# MCU_SUPPORT_CCU_HAS.net
KiCad netlist of a schematic drawn in Altium Designer
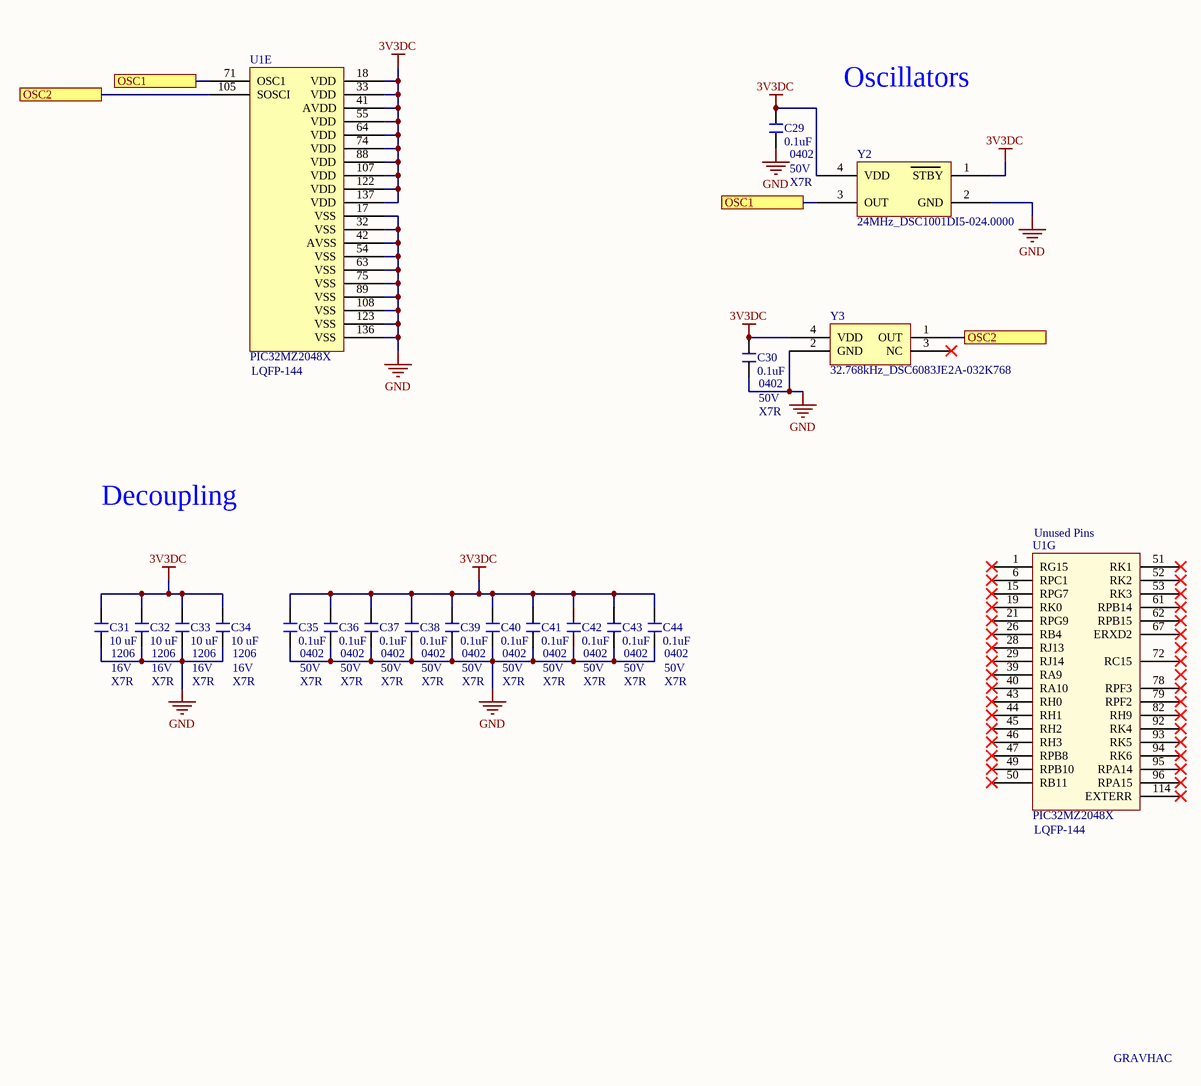
[diagram p0: MCU_SUPPORT_CCU_HAS.SchDoc]

(export (version "E")
  (design (tool "Eeschema 10.0.6"))
  (components
    (comp (ref "C29")
      (value "0.1uF")
      (footprint "NonPolar-0402")
      (libsource (lib "GravLib") (part "Cap - 0402"))
    )
    (comp (ref "C30")
      (value "0.1uF")
      (footprint "NonPolar-0402")
      (libsource (lib "GravLib") (part "Cap - 0402"))
    )
    (comp (ref "C31")
      (value "10 uF")
      (footprint "NONPOLAR-1206")
      (description "CGA5L1X7R1E106K160AE")
      (libsource (lib "GravLib") (part "Cap - 1206"))
    )
    (comp (ref "C32")
      (value "10 uF")
      (footprint "NONPOLAR-1206")
      (description "CGA5L1X7R1E106K160AE")
      (libsource (lib "GravLib") (part "Cap - 1206"))
    )
    (comp (ref "C33")
      (value "10 uF")
      (footprint "NONPOLAR-1206")
      (description "CGA5L1X7R1E106K160AE")
      (libsource (lib "GravLib") (part "Cap - 1206"))
    )
    (comp (ref "C34")
      (value "10 uF")
      (footprint "NONPOLAR-1206")
      (description "CGA5L1X7R1E106K160AE")
      (libsource (lib "GravLib") (part "Cap - 1206"))
    )
    (comp (ref "C35")
      (value "0.1uF")
      (footprint "NonPolar-0402")
      (libsource (lib "GravLib") (part "Cap - 0402"))
    )
    (comp (ref "C36")
      (value "0.1uF")
      (footprint "NonPolar-0402")
      (libsource (lib "GravLib") (part "Cap - 0402"))
    )
    (comp (ref "C37")
      (value "0.1uF")
      (footprint "NonPolar-0402")
      (libsource (lib "GravLib") (part "Cap - 0402"))
    )
    (comp (ref "C38")
      (value "0.1uF")
      (footprint "NonPolar-0402")
      (libsource (lib "GravLib") (part "Cap - 0402"))
    )
    (comp (ref "C39")
      (value "0.1uF")
      (footprint "NonPolar-0402")
      (libsource (lib "GravLib") (part "Cap - 0402"))
    )
    (comp (ref "C40")
      (value "0.1uF")
      (footprint "NonPolar-0402")
      (libsource (lib "GravLib") (part "Cap - 0402"))
    )
    (comp (ref "C41")
      (value "0.1uF")
      (footprint "NonPolar-0402")
      (libsource (lib "GravLib") (part "Cap - 0402"))
    )
    (comp (ref "C42")
      (value "0.1uF")
      (footprint "NonPolar-0402")
      (libsource (lib "GravLib") (part "Cap - 0402"))
    )
    (comp (ref "C43")
      (value "0.1uF")
      (footprint "NonPolar-0402")
      (libsource (lib "GravLib") (part "Cap - 0402"))
    )
    (comp (ref "C44")
      (value "0.1uF")
      (footprint "NonPolar-0402")
      (libsource (lib "GravLib") (part "Cap - 0402"))
    )
    (comp (ref "U1")
      (value "PIC32MZ2048X")
      (footprint "BIG_PIC32MZ")
      (libsource (lib "GravLib") (part "PIC32MZ2048X"))
    )
    (comp (ref "Y2")
      (value "24MHz_DSC1001DI5-024.0000")
      (footprint "12MHz_DSC1001DE2-012.0000")
      (libsource (lib "GravLib") (part "24MHz_DSC1001DI5-024.0000"))
    )
    (comp (ref "Y3")
      (value "32.768kHz_DSC6083JE2A-032K768")
      (footprint "32.768kHz_DSC6083JE2A-032K768")
      (libsource (lib "GravLib") (part "32.768kHz_DSC6083JE2A-032K768"))
    )
  )
  (nets
    (net (code "1") (name "/OSC1") (class "Default")
      (node (ref "U1") (pin "71") (pinfunction "OSC1_71") (pintype "passive"))
      (node (ref "Y2") (pin "3") (pinfunction "OUT_3") (pintype "passive"))
    )
    (net (code "2") (name "/OSC2") (class "Default")
      (node (ref "U1") (pin "105") (pinfunction "SOSCI_105") (pintype "passive"))
      (node (ref "Y3") (pin "1") (pinfunction "OUT_1") (pintype "passive"))
    )
    (net (code "3") (name "3V3DC") (class "Default")
      (node (ref "C29") (pin "2") (pinfunction "2_2") (pintype "passive"))
      (node (ref "C30") (pin "2") (pinfunction "2_2") (pintype "passive"))
      (node (ref "C31") (pin "2") (pinfunction "2_2") (pintype "passive"))
      (node (ref "C32") (pin "2") (pinfunction "2_2") (pintype "passive"))
      (node (ref "C33") (pin "2") (pinfunction "2_2") (pintype "passive"))
      (node (ref "C34") (pin "2") (pinfunction "2_2") (pintype "passive"))
      (node (ref "C35") (pin "2") (pinfunction "2_2") (pintype "passive"))
      (node (ref "C36") (pin "2") (pinfunction "2_2") (pintype "passive"))
      (node (ref "C37") (pin "2") (pinfunction "2_2") (pintype "passive"))
      (node (ref "C38") (pin "2") (pinfunction "2_2") (pintype "passive"))
      (node (ref "C39") (pin "2") (pinfunction "2_2") (pintype "passive"))
      (node (ref "C40") (pin "2") (pinfunction "2_2") (pintype "passive"))
      (node (ref "C41") (pin "2") (pinfunction "2_2") (pintype "passive"))
      (node (ref "C42") (pin "2") (pinfunction "2_2") (pintype "passive"))
      (node (ref "C43") (pin "2") (pinfunction "2_2") (pintype "passive"))
      (node (ref "C44") (pin "2") (pinfunction "2_2") (pintype "passive"))
      (node (ref "U1") (pin "107") (pinfunction "VDD_107") (pintype "passive"))
      (node (ref "U1") (pin "122") (pinfunction "VDD_122") (pintype "passive"))
      (node (ref "U1") (pin "137") (pinfunction "VDD_137") (pintype "passive"))
      (node (ref "U1") (pin "18") (pinfunction "VDD_18") (pintype "passive"))
      (node (ref "U1") (pin "33") (pinfunction "VDD_33") (pintype "passive"))
      (node (ref "U1") (pin "41") (pinfunction "AVDD_41") (pintype "passive"))
      (node (ref "U1") (pin "55") (pinfunction "VDD_55") (pintype "passive"))
      (node (ref "U1") (pin "64") (pinfunction "VDD_64") (pintype "passive"))
      (node (ref "U1") (pin "74") (pinfunction "VDD_74") (pintype "passive"))
      (node (ref "U1") (pin "88") (pinfunction "VDD_88") (pintype "passive"))
      (node (ref "Y2") (pin "1") (pinfunction "STBY_1") (pintype "passive"))
      (node (ref "Y2") (pin "4") (pinfunction "VDD_4") (pintype "passive"))
      (node (ref "Y3") (pin "4") (pinfunction "VDD_4") (pintype "passive"))
    )
    (net (code "4") (name "GND") (class "Default")
      (node (ref "C29") (pin "1") (pinfunction "1_1") (pintype "passive"))
      (node (ref "C30") (pin "1") (pinfunction "1_1") (pintype "passive"))
      (node (ref "C31") (pin "1") (pinfunction "1_1") (pintype "passive"))
      (node (ref "C32") (pin "1") (pinfunction "1_1") (pintype "passive"))
      (node (ref "C33") (pin "1") (pinfunction "1_1") (pintype "passive"))
      (node (ref "C34") (pin "1") (pinfunction "1_1") (pintype "passive"))
      (node (ref "C35") (pin "1") (pinfunction "1_1") (pintype "passive"))
      (node (ref "C36") (pin "1") (pinfunction "1_1") (pintype "passive"))
      (node (ref "C37") (pin "1") (pinfunction "1_1") (pintype "passive"))
      (node (ref "C38") (pin "1") (pinfunction "1_1") (pintype "passive"))
      (node (ref "C39") (pin "1") (pinfunction "1_1") (pintype "passive"))
      (node (ref "C40") (pin "1") (pinfunction "1_1") (pintype "passive"))
      (node (ref "C41") (pin "1") (pinfunction "1_1") (pintype "passive"))
      (node (ref "C42") (pin "1") (pinfunction "1_1") (pintype "passive"))
      (node (ref "C43") (pin "1") (pinfunction "1_1") (pintype "passive"))
      (node (ref "C44") (pin "1") (pinfunction "1_1") (pintype "passive"))
      (node (ref "U1") (pin "108") (pinfunction "VSS_108") (pintype "passive"))
      (node (ref "U1") (pin "123") (pinfunction "VSS_123") (pintype "passive"))
      (node (ref "U1") (pin "136") (pinfunction "VSS_136") (pintype "passive"))
      (node (ref "U1") (pin "17") (pinfunction "VSS_17") (pintype "passive"))
      (node (ref "U1") (pin "32") (pinfunction "VSS_32") (pintype "passive"))
      (node (ref "U1") (pin "42") (pinfunction "AVSS_42") (pintype "passive"))
      (node (ref "U1") (pin "54") (pinfunction "VSS_54") (pintype "passive"))
      (node (ref "U1") (pin "63") (pinfunction "VSS_63") (pintype "passive"))
      (node (ref "U1") (pin "75") (pinfunction "VSS_75") (pintype "passive"))
      (node (ref "U1") (pin "89") (pinfunction "VSS_89") (pintype "passive"))
      (node (ref "Y2") (pin "2") (pinfunction "GND_2") (pintype "passive"))
      (node (ref "Y3") (pin "2") (pinfunction "GND_2") (pintype "passive"))
    )
    (net (code "5") (name "unconnected-(U1G-ERXD2-Pad67)") (class "Default")
      (node (ref "U1") (pin "67") (pinfunction "ERXD2_67") (pintype "passive+no_connect"))
    )
    (net (code "6") (name "unconnected-(U1G-EXTERR-Pad114)") (class "Default")
      (node (ref "U1") (pin "114") (pinfunction "EXTERR_114") (pintype "passive+no_connect"))
    )
    (net (code "7") (name "unconnected-(U1G-RA9-Pad39)") (class "Default")
      (node (ref "U1") (pin "39") (pinfunction "RA9_39") (pintype "passive+no_connect"))
    )
    (net (code "8") (name "unconnected-(U1G-RA10-Pad40)") (class "Default")
      (node (ref "U1") (pin "40") (pinfunction "RA10_40") (pintype "passive+no_connect"))
    )
    (net (code "9") (name "unconnected-(U1G-RB4-Pad26)") (class "Default")
      (node (ref "U1") (pin "26") (pinfunction "RB4_26") (pintype "passive+no_connect"))
    )
    (net (code "10") (name "unconnected-(U1G-RB11-Pad50)") (class "Default")
      (node (ref "U1") (pin "50") (pinfunction "RB11_50") (pintype "passive+no_connect"))
    )
    (net (code "11") (name "unconnected-(U1G-RC15-Pad72)") (class "Default")
      (node (ref "U1") (pin "72") (pinfunction "RC15_72") (pintype "passive+no_connect"))
    )
    (net (code "12") (name "unconnected-(U1G-RG15-Pad1)") (class "Default")
      (node (ref "U1") (pin "1") (pinfunction "RG15_1") (pintype "passive+no_connect"))
    )
    (net (code "13") (name "unconnected-(U1G-RH0-Pad43)") (class "Default")
      (node (ref "U1") (pin "43") (pinfunction "RH0_43") (pintype "passive+no_connect"))
    )
    (net (code "14") (name "unconnected-(U1G-RH1-Pad44)") (class "Default")
      (node (ref "U1") (pin "44") (pinfunction "RH1_44") (pintype "passive+no_connect"))
    )
    (net (code "15") (name "unconnected-(U1G-RH2-Pad45)") (class "Default")
      (node (ref "U1") (pin "45") (pinfunction "RH2_45") (pintype "passive+no_connect"))
    )
    (net (code "16") (name "unconnected-(U1G-RH3-Pad46)") (class "Default")
      (node (ref "U1") (pin "46") (pinfunction "RH3_46") (pintype "passive+no_connect"))
    )
    (net (code "17") (name "unconnected-(U1G-RH9-Pad82)") (class "Default")
      (node (ref "U1") (pin "82") (pinfunction "RH9_82") (pintype "passive+no_connect"))
    )
    (net (code "18") (name "unconnected-(U1G-RJ13-Pad28)") (class "Default")
      (node (ref "U1") (pin "28") (pinfunction "RJ13_28") (pintype "passive+no_connect"))
    )
    (net (code "19") (name "unconnected-(U1G-RJ14-Pad29)") (class "Default")
      (node (ref "U1") (pin "29") (pinfunction "RJ14_29") (pintype "passive+no_connect"))
    )
    (net (code "20") (name "unconnected-(U1G-RK0-Pad19)") (class "Default")
      (node (ref "U1") (pin "19") (pinfunction "RK0_19") (pintype "passive+no_connect"))
    )
    (net (code "21") (name "unconnected-(U1G-RK1-Pad51)") (class "Default")
      (node (ref "U1") (pin "51") (pinfunction "RK1_51") (pintype "passive+no_connect"))
    )
    (net (code "22") (name "unconnected-(U1G-RK2-Pad52)") (class "Default")
      (node (ref "U1") (pin "52") (pinfunction "RK2_52") (pintype "passive+no_connect"))
    )
    (net (code "23") (name "unconnected-(U1G-RK3-Pad53)") (class "Default")
      (node (ref "U1") (pin "53") (pinfunction "RK3_53") (pintype "passive+no_connect"))
    )
    (net (code "24") (name "unconnected-(U1G-RK4-Pad92)") (class "Default")
      (node (ref "U1") (pin "92") (pinfunction "RK4_92") (pintype "passive+no_connect"))
    )
    (net (code "25") (name "unconnected-(U1G-RK5-Pad93)") (class "Default")
      (node (ref "U1") (pin "93") (pinfunction "RK5_93") (pintype "passive+no_connect"))
    )
    (net (code "26") (name "unconnected-(U1G-RK6-Pad94)") (class "Default")
      (node (ref "U1") (pin "94") (pinfunction "RK6_94") (pintype "passive+no_connect"))
    )
    (net (code "27") (name "unconnected-(U1G-RPA14-Pad95)") (class "Default")
      (node (ref "U1") (pin "95") (pinfunction "RPA14_95") (pintype "passive+no_connect"))
    )
    (net (code "28") (name "unconnected-(U1G-RPA15-Pad96)") (class "Default")
      (node (ref "U1") (pin "96") (pinfunction "RPA15_96") (pintype "passive+no_connect"))
    )
    (net (code "29") (name "unconnected-(U1G-RPB8-Pad47)") (class "Default")
      (node (ref "U1") (pin "47") (pinfunction "RPB8_47") (pintype "passive+no_connect"))
    )
    (net (code "30") (name "unconnected-(U1G-RPB10-Pad49)") (class "Default")
      (node (ref "U1") (pin "49") (pinfunction "RPB10_49") (pintype "passive+no_connect"))
    )
    (net (code "31") (name "unconnected-(U1G-RPB14-Pad61)") (class "Default")
      (node (ref "U1") (pin "61") (pinfunction "RPB14_61") (pintype "passive+no_connect"))
    )
    (net (code "32") (name "unconnected-(U1G-RPB15-Pad62)") (class "Default")
      (node (ref "U1") (pin "62") (pinfunction "RPB15_62") (pintype "passive+no_connect"))
    )
    (net (code "33") (name "unconnected-(U1G-RPC1-Pad6)") (class "Default")
      (node (ref "U1") (pin "6") (pinfunction "RPC1_6") (pintype "passive+no_connect"))
    )
    (net (code "34") (name "unconnected-(U1G-RPF2-Pad79)") (class "Default")
      (node (ref "U1") (pin "79") (pinfunction "RPF2_79") (pintype "passive+no_connect"))
    )
    (net (code "35") (name "unconnected-(U1G-RPF3-Pad78)") (class "Default")
      (node (ref "U1") (pin "78") (pinfunction "RPF3_78") (pintype "passive+no_connect"))
    )
    (net (code "36") (name "unconnected-(U1G-RPG7-Pad15)") (class "Default")
      (node (ref "U1") (pin "15") (pinfunction "RPG7_15") (pintype "passive+no_connect"))
    )
    (net (code "37") (name "unconnected-(U1G-RPG9-Pad21)") (class "Default")
      (node (ref "U1") (pin "21") (pinfunction "RPG9_21") (pintype "passive+no_connect"))
    )
    (net (code "38") (name "unconnected-(Y3-NC-Pad3)") (class "Default")
      (node (ref "Y3") (pin "3") (pinfunction "NC_3") (pintype "passive+no_connect"))
    )
  )
)
